# rpi-cc2538-uart.net
KiCad netlist of a schematic drawn in EAGLE
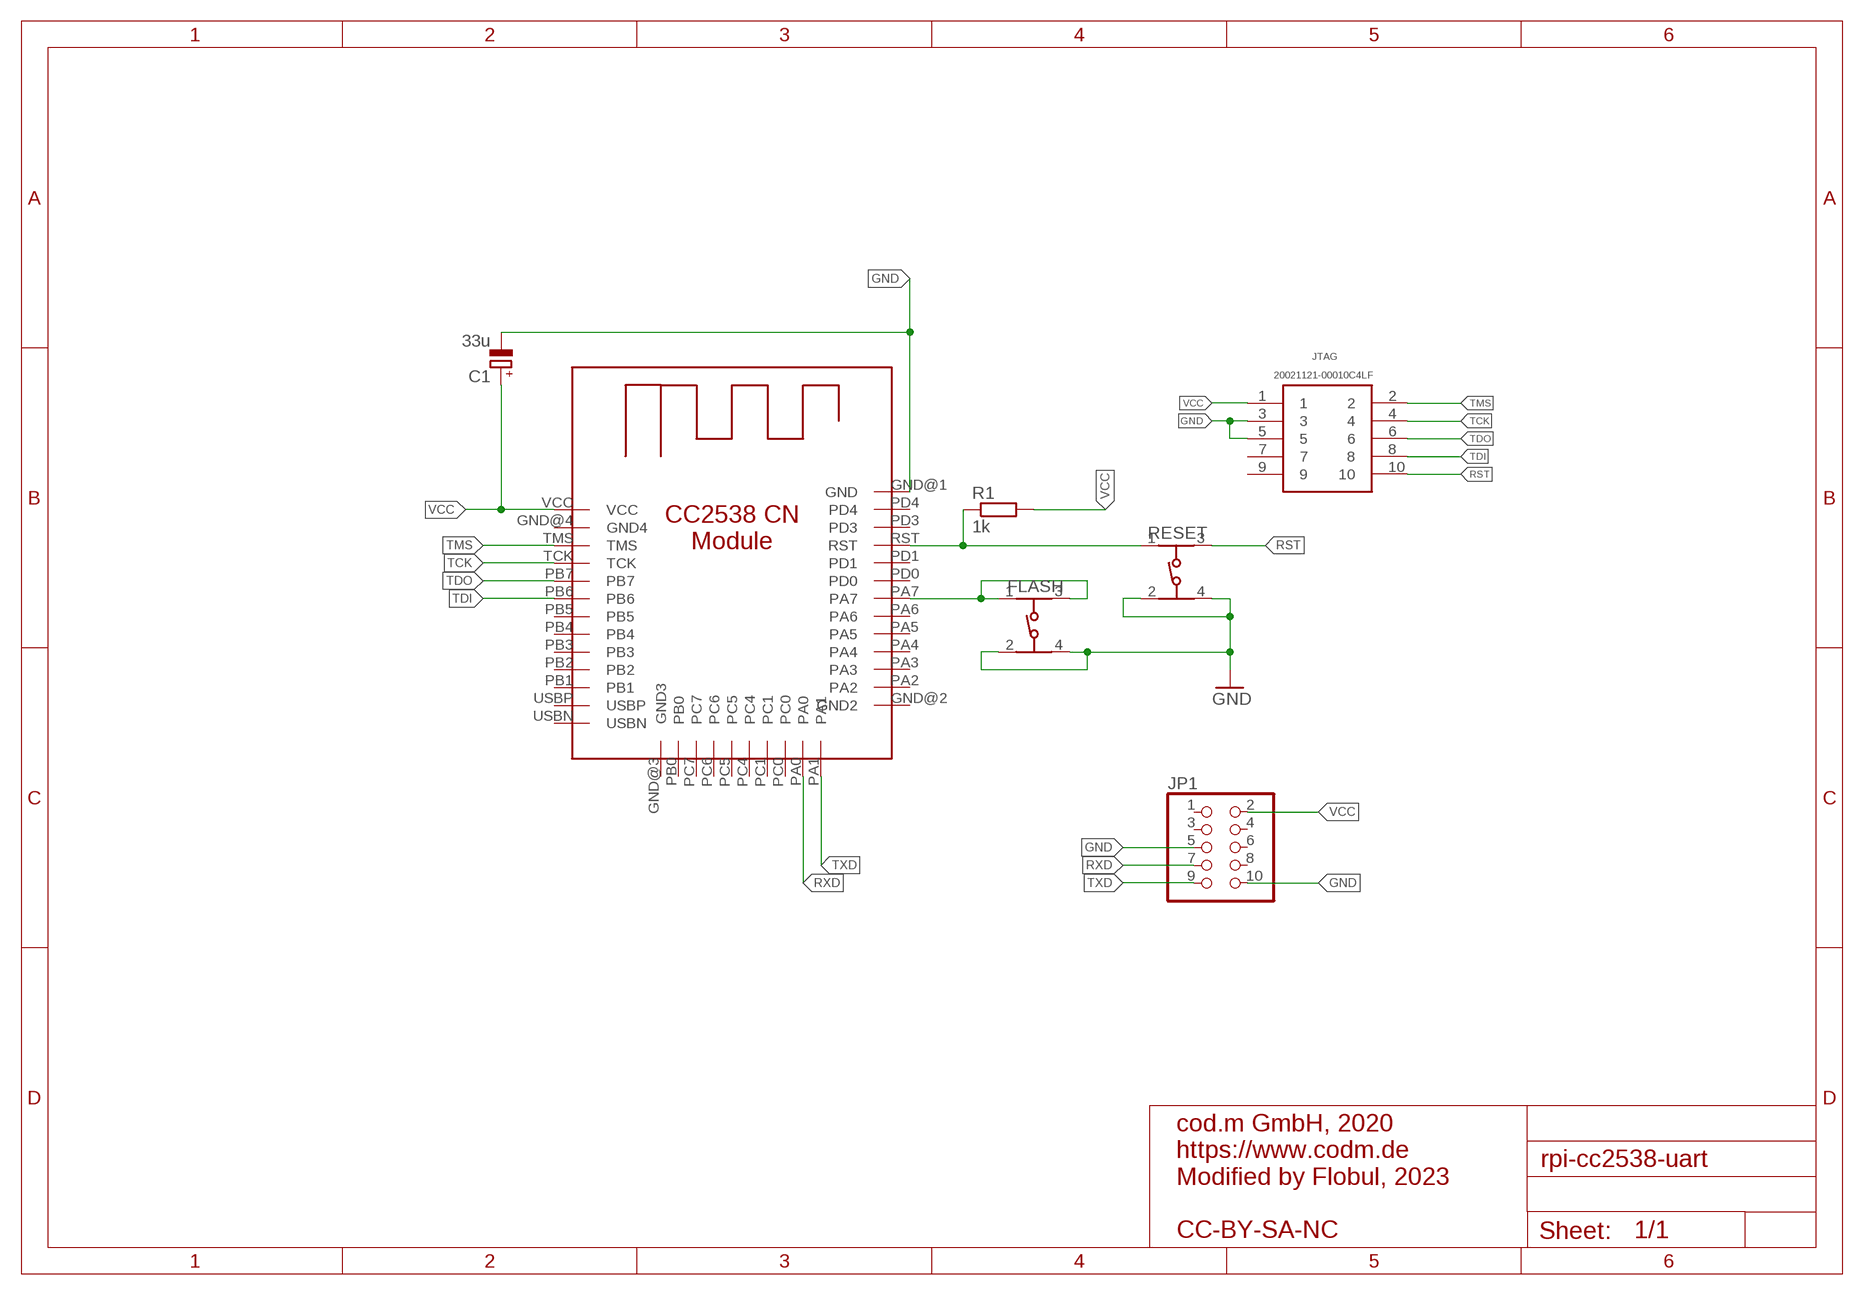
[diagram p0: schematic, sheet 1]

(export (version "E")
  (design (tool "Eeschema 10.0.6"))
  (components
    (comp (ref "C1")
      (value "33u")
      (footprint "eagle-import:A_3216-18W")
      (libsource (lib "eagle-import") (part "CPOL-EUA/3216-18W"))
    )
    (comp (ref "FLASH")
      (value "434153017835")
      (footprint "eagle-import:434153017835")
      (libsource (lib "eagle-import") (part "434153017835"))
    )
    (comp (ref "JP1")
      (value "PINHD-2X5")
      (footprint "eagle-import:2X05")
      (libsource (lib "eagle-import") (part "PINHD-2X5"))
    )
    (comp (ref "JTAG")
      (value "20021121-00010C4LF")
      (footprint "eagle-import:2002112100010C4LF")
      (fields (field (name "MOUSER_PART_NUMBER") "649-202112100010C4LF"))
      (libsource (lib "eagle-import") (part "20021121-00010C4LF"))
    )
    (comp (ref "R1")
      (value "1k")
      (footprint "eagle-import:R0805")
      (libsource (lib "eagle-import") (part "R-EU_R0805"))
    )
    (comp (ref "RESET")
      (value "434153017835")
      (footprint "eagle-import:434153017835")
      (libsource (lib "eagle-import") (part "434153017835"))
    )
    (comp (ref "U$1")
      (value "CC2538-CN")
      (footprint "eagle-import:CC2538-CN")
      (libsource (lib "eagle-import") (part "CC2538-CN"))
    )
  )
  (nets
    (net (code "1") (name "GND") (class "Default")
      (node (ref "C1") (pin "-") (pinfunction "-_-") (pintype "passive"))
      (node (ref "FLASH") (pin "2") (pinfunction "3_2") (pintype "passive"))
      (node (ref "FLASH") (pin "4") (pinfunction "4_4") (pintype "passive"))
      (node (ref "JP1") (pin "10") (pinfunction "10_10") (pintype "passive"))
      (node (ref "JP1") (pin "5") (pinfunction "5_5") (pintype "passive"))
      (node (ref "JTAG") (pin "3") (pinfunction "3_3") (pintype "bidirectional"))
      (node (ref "JTAG") (pin "5") (pinfunction "5_5") (pintype "bidirectional"))
      (node (ref "RESET") (pin "2") (pinfunction "3_2") (pintype "passive"))
      (node (ref "RESET") (pin "4") (pinfunction "4_4") (pintype "passive"))
      (node (ref "U$1") (pin "GND@1") (pinfunction "GND_GND@1") (pintype "bidirectional"))
    )
    (net (code "2") (name "Net-(FLASH-2)") (class "Default")
      (node (ref "FLASH") (pin "1") (pinfunction "1_1") (pintype "passive"))
      (node (ref "FLASH") (pin "3") (pinfunction "2_3") (pintype "passive"))
      (node (ref "U$1") (pin "PA7") (pinfunction "PA7_PA7") (pintype "bidirectional"))
    )
    (net (code "3") (name "RST") (class "Default")
      (node (ref "JTAG") (pin "10") (pinfunction "10_10") (pintype "bidirectional"))
      (node (ref "R1") (pin "1") (pinfunction "1_1") (pintype "passive"))
      (node (ref "RESET") (pin "1") (pinfunction "1_1") (pintype "passive"))
      (node (ref "RESET") (pin "3") (pinfunction "2_3") (pintype "passive"))
      (node (ref "U$1") (pin "RST") (pinfunction "RST_RST") (pintype "bidirectional"))
    )
    (net (code "4") (name "RXD") (class "Default")
      (node (ref "JP1") (pin "7") (pinfunction "7_7") (pintype "passive"))
      (node (ref "U$1") (pin "PA0") (pinfunction "PA0_PA0") (pintype "bidirectional"))
    )
    (net (code "5") (name "TCK") (class "Default")
      (node (ref "JTAG") (pin "4") (pinfunction "4_4") (pintype "bidirectional"))
      (node (ref "U$1") (pin "TCK") (pinfunction "TCK_TCK") (pintype "bidirectional"))
    )
    (net (code "6") (name "TDI") (class "Default")
      (node (ref "JTAG") (pin "8") (pinfunction "8_8") (pintype "bidirectional"))
      (node (ref "U$1") (pin "PB6") (pinfunction "PB6_PB6") (pintype "bidirectional"))
    )
    (net (code "7") (name "TDO") (class "Default")
      (node (ref "JTAG") (pin "6") (pinfunction "6_6") (pintype "bidirectional"))
      (node (ref "U$1") (pin "PB7") (pinfunction "PB7_PB7") (pintype "bidirectional"))
    )
    (net (code "8") (name "TMS") (class "Default")
      (node (ref "JTAG") (pin "2") (pinfunction "2_2") (pintype "bidirectional"))
      (node (ref "U$1") (pin "TMS") (pinfunction "TMS_TMS") (pintype "bidirectional"))
    )
    (net (code "9") (name "TXD") (class "Default")
      (node (ref "JP1") (pin "9") (pinfunction "9_9") (pintype "passive"))
      (node (ref "U$1") (pin "PA1") (pinfunction "PA1_PA1") (pintype "bidirectional"))
    )
    (net (code "10") (name "VCC") (class "Default")
      (node (ref "C1") (pin "+") (pinfunction "+_+") (pintype "passive"))
      (node (ref "JP1") (pin "2") (pinfunction "2_2") (pintype "passive"))
      (node (ref "JTAG") (pin "1") (pinfunction "1_1") (pintype "bidirectional"))
      (node (ref "R1") (pin "2") (pinfunction "2_2") (pintype "passive"))
      (node (ref "U$1") (pin "VCC") (pinfunction "VCC_VCC") (pintype "bidirectional"))
    )
    (net (code "11") (name "unconnected-(JP1-Pad1)") (class "Default")
      (node (ref "JP1") (pin "1") (pinfunction "1_1") (pintype "passive"))
    )
    (net (code "12") (name "unconnected-(JP1-Pad3)") (class "Default")
      (node (ref "JP1") (pin "3") (pinfunction "3_3") (pintype "passive"))
    )
    (net (code "13") (name "unconnected-(JP1-Pad4)") (class "Default")
      (node (ref "JP1") (pin "4") (pinfunction "4_4") (pintype "passive"))
    )
    (net (code "14") (name "unconnected-(JP1-Pad6)") (class "Default")
      (node (ref "JP1") (pin "6") (pinfunction "6_6") (pintype "passive"))
    )
    (net (code "15") (name "unconnected-(JP1-Pad8)") (class "Default")
      (node (ref "JP1") (pin "8") (pinfunction "8_8") (pintype "passive"))
    )
    (net (code "16") (name "unconnected-(JTAG-Pad7)") (class "Default")
      (node (ref "JTAG") (pin "7") (pinfunction "7_7") (pintype "bidirectional"))
    )
    (net (code "17") (name "unconnected-(JTAG-Pad9)") (class "Default")
      (node (ref "JTAG") (pin "9") (pinfunction "9_9") (pintype "bidirectional"))
    )
    (net (code "18") (name "unconnected-(U$1-GND2-PadGND@2)") (class "Default")
      (node (ref "U$1") (pin "GND@2") (pinfunction "GND2_GND@2") (pintype "bidirectional"))
    )
    (net (code "19") (name "unconnected-(U$1-GND3-PadGND@3)") (class "Default")
      (node (ref "U$1") (pin "GND@3") (pinfunction "GND3_GND@3") (pintype "bidirectional"))
    )
    (net (code "20") (name "unconnected-(U$1-GND4-PadGND@4)") (class "Default")
      (node (ref "U$1") (pin "GND@4") (pinfunction "GND4_GND@4") (pintype "bidirectional"))
    )
    (net (code "21") (name "unconnected-(U$1-PadPA2)") (class "Default")
      (node (ref "U$1") (pin "PA2") (pinfunction "PA2_PA2") (pintype "bidirectional"))
    )
    (net (code "22") (name "unconnected-(U$1-PadPA3)") (class "Default")
      (node (ref "U$1") (pin "PA3") (pinfunction "PA3_PA3") (pintype "bidirectional"))
    )
    (net (code "23") (name "unconnected-(U$1-PadPA4)") (class "Default")
      (node (ref "U$1") (pin "PA4") (pinfunction "PA4_PA4") (pintype "bidirectional"))
    )
    (net (code "24") (name "unconnected-(U$1-PadPA5)") (class "Default")
      (node (ref "U$1") (pin "PA5") (pinfunction "PA5_PA5") (pintype "bidirectional"))
    )
    (net (code "25") (name "unconnected-(U$1-PadPA6)") (class "Default")
      (node (ref "U$1") (pin "PA6") (pinfunction "PA6_PA6") (pintype "bidirectional"))
    )
    (net (code "26") (name "unconnected-(U$1-PadPB0)") (class "Default")
      (node (ref "U$1") (pin "PB0") (pinfunction "PB0_PB0") (pintype "bidirectional"))
    )
    (net (code "27") (name "unconnected-(U$1-PadPB1)") (class "Default")
      (node (ref "U$1") (pin "PB1") (pinfunction "PB1_PB1") (pintype "bidirectional"))
    )
    (net (code "28") (name "unconnected-(U$1-PadPB2)") (class "Default")
      (node (ref "U$1") (pin "PB2") (pinfunction "PB2_PB2") (pintype "bidirectional"))
    )
    (net (code "29") (name "unconnected-(U$1-PadPB3)") (class "Default")
      (node (ref "U$1") (pin "PB3") (pinfunction "PB3_PB3") (pintype "bidirectional"))
    )
    (net (code "30") (name "unconnected-(U$1-PadPB4)") (class "Default")
      (node (ref "U$1") (pin "PB4") (pinfunction "PB4_PB4") (pintype "bidirectional"))
    )
    (net (code "31") (name "unconnected-(U$1-PadPB5)") (class "Default")
      (node (ref "U$1") (pin "PB5") (pinfunction "PB5_PB5") (pintype "bidirectional"))
    )
    (net (code "32") (name "unconnected-(U$1-PadPC0)") (class "Default")
      (node (ref "U$1") (pin "PC0") (pinfunction "PC0_PC0") (pintype "bidirectional"))
    )
    (net (code "33") (name "unconnected-(U$1-PadPC1)") (class "Default")
      (node (ref "U$1") (pin "PC1") (pinfunction "PC1_PC1") (pintype "bidirectional"))
    )
    (net (code "34") (name "unconnected-(U$1-PadPC4)") (class "Default")
      (node (ref "U$1") (pin "PC4") (pinfunction "PC4_PC4") (pintype "bidirectional"))
    )
    (net (code "35") (name "unconnected-(U$1-PadPC5)") (class "Default")
      (node (ref "U$1") (pin "PC5") (pinfunction "PC5_PC5") (pintype "bidirectional"))
    )
    (net (code "36") (name "unconnected-(U$1-PadPC6)") (class "Default")
      (node (ref "U$1") (pin "PC6") (pinfunction "PC6_PC6") (pintype "bidirectional"))
    )
    (net (code "37") (name "unconnected-(U$1-PadPC7)") (class "Default")
      (node (ref "U$1") (pin "PC7") (pinfunction "PC7_PC7") (pintype "bidirectional"))
    )
    (net (code "38") (name "unconnected-(U$1-PadPD0)") (class "Default")
      (node (ref "U$1") (pin "PD0") (pinfunction "PD0_PD0") (pintype "bidirectional"))
    )
    (net (code "39") (name "unconnected-(U$1-PadPD1)") (class "Default")
      (node (ref "U$1") (pin "PD1") (pinfunction "PD1_PD1") (pintype "bidirectional"))
    )
    (net (code "40") (name "unconnected-(U$1-PadPD3)") (class "Default")
      (node (ref "U$1") (pin "PD3") (pinfunction "PD3_PD3") (pintype "bidirectional"))
    )
    (net (code "41") (name "unconnected-(U$1-PadPD4)") (class "Default")
      (node (ref "U$1") (pin "PD4") (pinfunction "PD4_PD4") (pintype "bidirectional"))
    )
    (net (code "42") (name "unconnected-(U$1-PadUSBN)") (class "Default")
      (node (ref "U$1") (pin "USBN") (pinfunction "USBN_USBN") (pintype "bidirectional"))
    )
    (net (code "43") (name "unconnected-(U$1-PadUSBP)") (class "Default")
      (node (ref "U$1") (pin "USBP") (pinfunction "USBP_USBP") (pintype "bidirectional"))
    )
  )
)
